# 02_MCU.net
KiCad netlist of a schematic drawn in Altium Designer
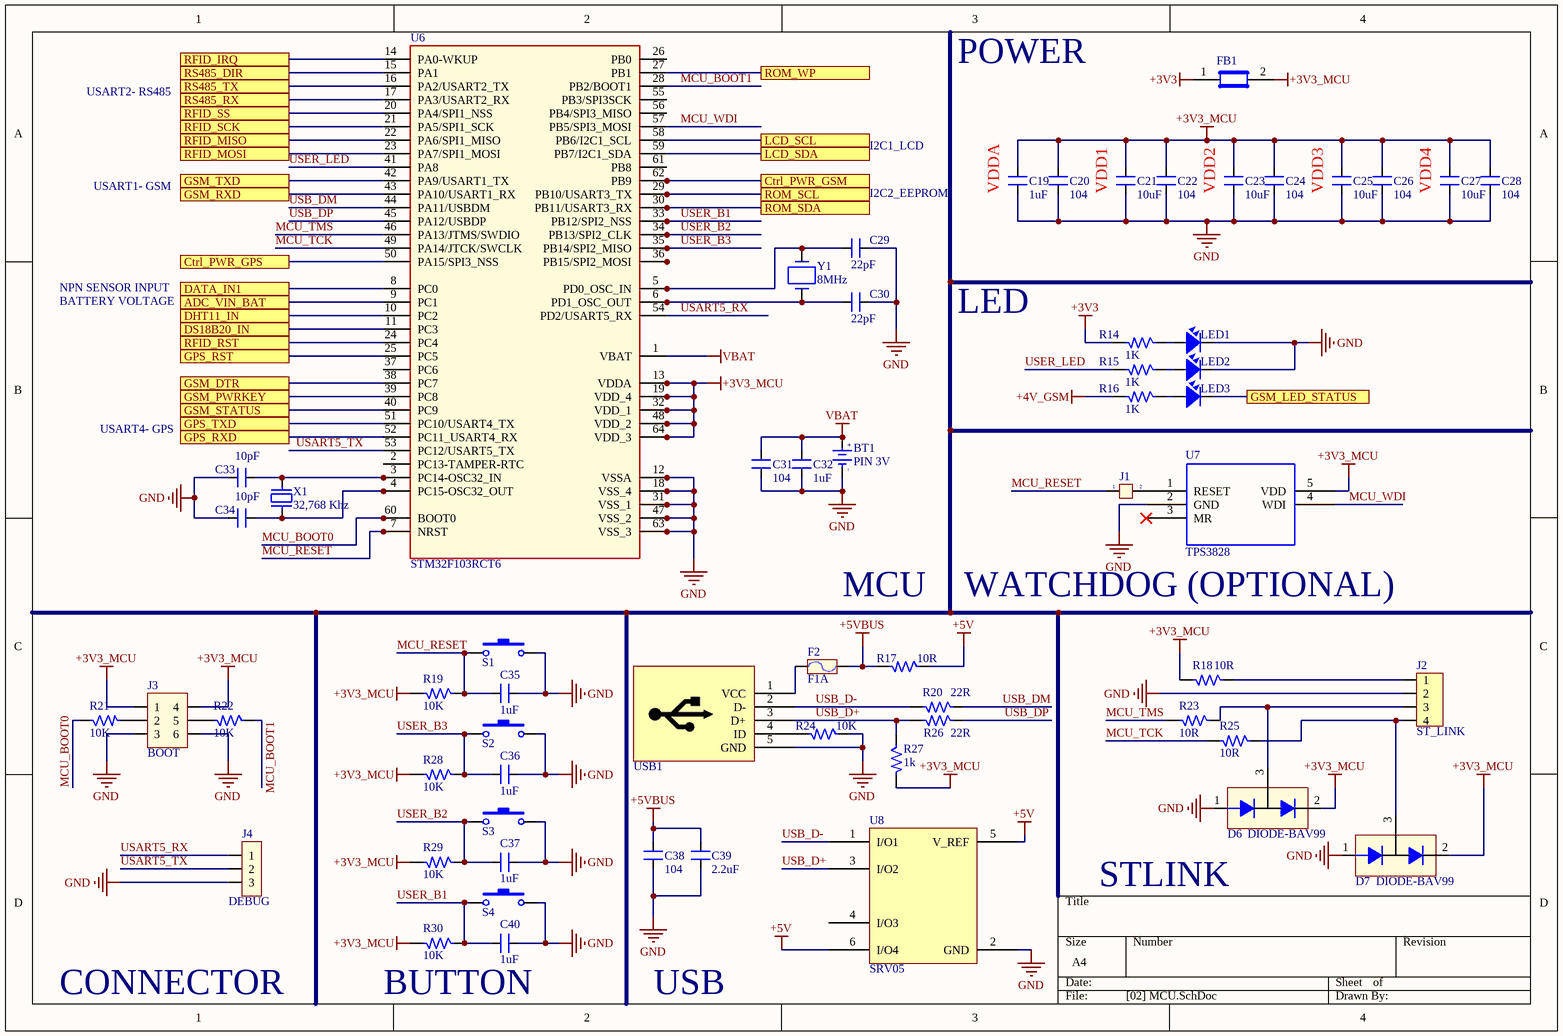
[diagram p0: [02] MCU.SchDoc]

(export (version "E")
  (design (tool "Eeschema 10.0.6"))
  (components
    (comp (ref "BT1")
      (value "PIN 3V")
      (footprint "CR1220 SMD")
      (description "Battery 3VDC")
      (libsource (lib "My Library") (part "PIN 3V"))
    )
    (comp (ref "C19")
      (value "1uF")
      (footprint "C0603 SMT")
      (description "Cap SMD")
      (libsource (lib "GPS_Traking_V1_1") (part "CM"))
    )
    (comp (ref "C20")
      (value "104")
      (footprint "C0603 SMT")
      (description "Cap SMD")
      (libsource (lib "GPS_Traking_V1_1") (part "CM"))
    )
    (comp (ref "C21")
      (value "10uF")
      (footprint "C0603 SMT")
      (description "Cap SMD")
      (libsource (lib "GPS_Traking_V1_1") (part "CM"))
    )
    (comp (ref "C22")
      (value "104")
      (footprint "C0603 SMT")
      (description "Cap SMD")
      (libsource (lib "GPS_Traking_V1_1") (part "CM"))
    )
    (comp (ref "C23")
      (value "10uF")
      (footprint "C0603 SMT")
      (description "Cap SMD")
      (libsource (lib "GPS_Traking_V1_1") (part "CM"))
    )
    (comp (ref "C24")
      (value "104")
      (footprint "C0603 SMT")
      (description "Cap SMD")
      (libsource (lib "GPS_Traking_V1_1") (part "CM"))
    )
    (comp (ref "C25")
      (value "10uF")
      (footprint "C0603 SMT")
      (description "Cap SMD")
      (libsource (lib "GPS_Traking_V1_1") (part "CM"))
    )
    (comp (ref "C26")
      (value "104")
      (footprint "C0603 SMT")
      (description "Cap SMD")
      (libsource (lib "GPS_Traking_V1_1") (part "CM"))
    )
    (comp (ref "C27")
      (value "10uF")
      (footprint "C0603 SMT")
      (description "Cap SMD")
      (libsource (lib "GPS_Traking_V1_1") (part "CM"))
    )
    (comp (ref "C28")
      (value "104")
      (footprint "C0603 SMT")
      (description "Cap SMD")
      (libsource (lib "GPS_Traking_V1_1") (part "CM"))
    )
    (comp (ref "C29")
      (value "22pF")
      (footprint "C0603 SMT")
      (description "Cap SMD")
      (libsource (lib "GPS_Traking_V1_1") (part "CM"))
    )
    (comp (ref "C30")
      (value "22pF")
      (footprint "GPS_Traking_V1_1:C0603 SMT")
      (description "Cap SMD")
      (libsource (lib "My Library") (part "CM"))
    )
    (comp (ref "C31")
      (value "104")
      (footprint "C0603 SMT")
      (description "Cap SMD")
      (libsource (lib "GPS_Traking_V1_1") (part "CM"))
    )
    (comp (ref "C32")
      (value "1uF")
      (footprint "GPS_Traking_V1_1:C0603 SMT")
      (description "Cap SMD")
      (libsource (lib "My Library") (part "CM"))
    )
    (comp (ref "C33")
      (value "10pF")
      (footprint "C0603 SMT")
      (description "Cap SMD")
      (libsource (lib "GPS_Traking_V1_1") (part "CM"))
    )
    (comp (ref "C34")
      (value "10pF")
      (footprint "C0603 SMT")
      (description "Cap SMD")
      (libsource (lib "GPS_Traking_V1_1") (part "CM"))
    )
    (comp (ref "C35")
      (value "1uF")
      (footprint "CAP_0805")
      (description "Cap SMD")
      (libsource (lib "GPS_Traking_V1_1") (part "CM"))
    )
    (comp (ref "C36")
      (value "1uF")
      (footprint "CAP_0805")
      (description "Cap SMD")
      (libsource (lib "GPS_Traking_V1_1") (part "CM"))
    )
    (comp (ref "C37")
      (value "1uF")
      (footprint "CAP_0805")
      (description "Cap SMD")
      (libsource (lib "GPS_Traking_V1_1") (part "CM"))
    )
    (comp (ref "C38")
      (value "104")
      (footprint "C0603 SMT")
      (description "Cap SMD")
      (libsource (lib "GPS_Traking_V1_1") (part "CM"))
    )
    (comp (ref "C39")
      (value "2.2uF")
      (footprint "RES-SMD-1210")
      (description "Cap SMD")
      (libsource (lib "My Library") (part "CM"))
    )
    (comp (ref "C40")
      (value "1uF")
      (footprint "CAP_0805")
      (description "Cap SMD")
      (libsource (lib "GPS_Traking_V1_1") (part "CM"))
    )
    (comp (ref "D6")
      (value "DIODE-BAV99")
      (footprint "SOT23")
      (description "ZENER, SOT23,")
      (fields
        (field (name "MANUFACTURER") "ON Semiconductor / Fairchild")
        (field (name "MANUFACTURER PART NUMBER") "BAV99")
        (field (name ".CREATOR") "LeKhaLinh")
        (field (name ".CHECKPCB") "LeKhaLinh")
        (field (name ".CHECKSCH") "LeKhaLinh")
      )
      (libsource (lib "GPS_Traking_V1_1") (part "DIODE-BAV99"))
    )
    (comp (ref "D7")
      (value "DIODE-BAV99")
      (footprint "SOT23")
      (description "ZENER, SOT23,")
      (fields
        (field (name "MANUFACTURER") "ON Semiconductor / Fairchild")
        (field (name "MANUFACTURER PART NUMBER") "BAV99")
        (field (name ".CREATOR") "LeKhaLinh")
        (field (name ".CHECKPCB") "LeKhaLinh")
        (field (name ".CHECKSCH") "LeKhaLinh")
      )
      (libsource (lib "GPS_Traking_V1_1") (part "DIODE-BAV99"))
    )
    (comp (ref "F2")
      (value "F1A")
      (footprint "RES-SMD-1812")
      (description "Fuse")
      (fields (field (name "DESIGNED BY") "VanDungEvn"))
      (libsource (lib "My Library") (part "Fuse"))
    )
    (comp (ref "FB1")
      (value "BLM21PG600SN1D")
      (footprint "GPS_Traking_V1_1:R0805")
      (description "Ferrite Bead")
      (libsource (lib "khapham") (part "Ferrite Bead"))
    )
    (comp (ref "J1")
      (value "watdog")
      (footprint "JP2")
      (description "Jumper 2")
      (libsource (lib "GPS_Traking_V1_1") (part "JP 2"))
    )
    (comp (ref "J2")
      (value "ST_LINK")
      (footprint "CON_4P")
      (description "Header IDC, 4 x 1 Pin Vertical 2.54mm Pitch (Non-Boxed, Male)")
      (fields
        (field (name "MANUFACTURER") "Würth Elektronik eiSos GmbH")
        (field (name "PARTNO") "613002143121")
        (field (name "CREATED BY") "Karrer Zheng")
      )
      (libsource (lib "My Library") (part "Header4"))
    )
    (comp (ref "J3")
      (value "BOOT")
      (footprint "JP3x2")
      (description "Connector 3x2")
      (libsource (lib "GPS_Traking_V1_1") (part "JP3x2"))
    )
    (comp (ref "J4")
      (value "DEBUG")
      (footprint "JP3")
      (description "Jumper 3")
      (libsource (lib "My Library") (part "JP3"))
    )
    (comp (ref "LED1")
      (value "LED")
      (footprint "LED-0805-Green")
      (description "LED Single colour Green and Red")
      (libsource (lib "My Library") (part "LED"))
    )
    (comp (ref "LED2")
      (value "LED")
      (footprint "LED-0805-Yellow")
      (description "LED Single colour Green and Red")
      (libsource (lib "My Library") (part "LED"))
    )
    (comp (ref "LED3")
      (value "LED")
      (footprint "LED-0805-Red")
      (description "LED Single colour Green and Red")
      (libsource (lib "My Library") (part "LED"))
    )
    (comp (ref "R14")
      (value "1K")
      (footprint "RES-SMD-0805")
      (description "Resistor SMD")
      (libsource (lib "GPS_Traking_V1_1") (part "RM"))
    )
    (comp (ref "R15")
      (value "1K")
      (footprint "RES-SMD-0805")
      (description "Resistor SMD")
      (libsource (lib "GPS_Traking_V1_1") (part "RM"))
    )
    (comp (ref "R16")
      (value "1K")
      (footprint "RES-SMD-0805")
      (description "Resistor SMD")
      (libsource (lib "GPS_Traking_V1_1") (part "RM"))
    )
    (comp (ref "R17")
      (value "10R")
      (footprint "RES-SMD-0805")
      (description "Resistor SMD")
      (libsource (lib "GPS_Traking_V1_1") (part "RM"))
    )
    (comp (ref "R18")
      (value "10R")
      (footprint "RES-SMD-0805")
      (description "Resistor SMD")
      (libsource (lib "GPS_Traking_V1_1") (part "RM"))
    )
    (comp (ref "R19")
      (value "10K")
      (footprint "RES-SMD-0805")
      (description "Resistor SMD")
      (libsource (lib "GPS_Traking_V1_1") (part "RM"))
    )
    (comp (ref "R20")
      (value "22R")
      (footprint "RES-SMD-0603")
      (description "Resistor SMD")
      (libsource (lib "GPS_Traking_V1_1") (part "RM"))
    )
    (comp (ref "R21")
      (value "10K")
      (footprint "R0603 -SMT")
      (description "Resistor SMD")
      (libsource (lib "GPS_Traking_V1_1") (part "RM"))
    )
    (comp (ref "R22")
      (value "10K")
      (footprint "R0603 -SMT")
      (description "Resistor SMD")
      (libsource (lib "GPS_Traking_V1_1") (part "RM"))
    )
    (comp (ref "R23")
      (value "10R")
      (footprint "RES-SMD-0805")
      (description "Resistor SMD")
      (libsource (lib "GPS_Traking_V1_1") (part "RM"))
    )
    (comp (ref "R24")
      (value "10K")
      (footprint "RES-SMD-0603")
      (description "Resistor SMD")
      (libsource (lib "GPS_Traking_V1_1") (part "RM"))
    )
    (comp (ref "R25")
      (value "10R")
      (footprint "RES-SMD-0805")
      (description "Resistor SMD")
      (libsource (lib "GPS_Traking_V1_1") (part "RM"))
    )
    (comp (ref "R26")
      (value "22R")
      (footprint "RES-SMD-0603")
      (description "Resistor SMD")
      (libsource (lib "GPS_Traking_V1_1") (part "RM"))
    )
    (comp (ref "R27")
      (value "1k")
      (footprint "RES-SMD-0603")
      (description "Resistor SMD")
      (libsource (lib "GPS_Traking_V1_1") (part "RM"))
    )
    (comp (ref "R28")
      (value "10K")
      (footprint "RES-SMD-0805")
      (description "Resistor SMD")
      (libsource (lib "GPS_Traking_V1_1") (part "RM"))
    )
    (comp (ref "R29")
      (value "10K")
      (footprint "RES-SMD-0805")
      (description "Resistor SMD")
      (libsource (lib "GPS_Traking_V1_1") (part "RM"))
    )
    (comp (ref "R30")
      (value "10K")
      (footprint "RES-SMD-0805")
      (description "Resistor SMD")
      (libsource (lib "GPS_Traking_V1_1") (part "RM"))
    )
    (comp (ref "S1")
      (value "SW-SMD")
      (footprint "SW-SMD")
      (description "Switch")
      (fields (field (name "PUBLISHER") "Altium Limited"))
      (libsource (lib "My Library") (part "SW-SMD"))
    )
    (comp (ref "S2")
      (value "SW-SMD")
      (footprint "BUTTON NGHIENG")
      (description "Switch")
      (fields (field (name "PUBLISHER") "Altium Limited"))
      (libsource (lib "My Library") (part "SW-SMD"))
    )
    (comp (ref "S3")
      (value "SW-SMD")
      (footprint "BUTTON NGHIENG")
      (description "Switch")
      (fields (field (name "PUBLISHER") "Altium Limited"))
      (libsource (lib "My Library") (part "SW-SMD"))
    )
    (comp (ref "S4")
      (value "SW-SMD")
      (footprint "BUTTON NGHIENG")
      (description "Switch")
      (fields (field (name "PUBLISHER") "Altium Limited"))
      (libsource (lib "My Library") (part "SW-SMD"))
    )
    (comp (ref "U6")
      (value "STM32F103RCT6")
      (footprint "LQFP-64")
      (description "MCU 32BIT 256KB FLASH 64LQFP")
      (libsource (lib "GPS_Traking_V1_1") (part "STM32F103RCT6"))
    )
    (comp (ref "U7")
      (value "TPS3828")
      (footprint "TPS3828")
      (libsource (lib "GPS_Traking_V1_1") (part "TPS3828"))
    )
    (comp (ref "U8")
      (value "SRV05")
      (footprint "SOT23-6")
      (description "TVS DIODE 5V")
      (libsource (lib "My Library") (part "SRV05"))
    )
    (comp (ref "USB1") (value "USB") (footprint "USB-B-Mini") (libsource (lib "My Library") (part "USB-M")))
    (comp (ref "X1")
      (value "32,768 Khz")
      (footprint "XT32kn")
      (description "Crystal 32,768kHz for timer real")
      (libsource (lib "GPS_Traking_V1_1") (part "XT32k"))
    )
    (comp (ref "Y1")
      (value "8MHz")
      (footprint "GPS_Traking_V1_1:ABM7_v1_1_BIG")
      (description "CRYSTAL 16MHZ 18PF SMD")
      (fields
        (field (name "MANUFACTURER") "Abracon LLC")
        (field (name "MANUFACTURER PART NUMBER") "ABM7-16.000MHZ-D2Y-T")
        (field (name ".CREATOR") "MM")
        (field (name ".CHECKED PCB") "RF")
        (field (name ".CHECKED SCH") "RF")
      )
      (libsource (lib "GPS_Traking_V1_1") (part "ABM7-16.000MHZ-D2Y-T"))
    )
  )
  (nets
    (net (code "1") (name "+3V3") (class "Default")
      (node (ref "FB1") (pin "1") (pinfunction "1_1") (pintype "passive"))
      (node (ref "R14") (pin "2") (pinfunction "2_2") (pintype "passive"))
    )
    (net (code "2") (name "+3V3_MCU") (class "Default")
      (node (ref "C19") (pin "2") (pinfunction "2_2") (pintype "passive"))
      (node (ref "C20") (pin "2") (pinfunction "2_2") (pintype "passive"))
      (node (ref "C21") (pin "2") (pinfunction "2_2") (pintype "passive"))
      (node (ref "C22") (pin "2") (pinfunction "2_2") (pintype "passive"))
      (node (ref "C23") (pin "2") (pinfunction "2_2") (pintype "passive"))
      (node (ref "C24") (pin "2") (pinfunction "2_2") (pintype "passive"))
      (node (ref "C25") (pin "2") (pinfunction "2_2") (pintype "passive"))
      (node (ref "C26") (pin "2") (pinfunction "2_2") (pintype "passive"))
      (node (ref "C27") (pin "2") (pinfunction "2_2") (pintype "passive"))
      (node (ref "C28") (pin "2") (pinfunction "2_2") (pintype "passive"))
      (node (ref "D6") (pin "2") (pinfunction "2_2") (pintype "passive"))
      (node (ref "D7") (pin "2") (pinfunction "2_2") (pintype "passive"))
      (node (ref "FB1") (pin "2") (pinfunction "2_2") (pintype "passive"))
      (node (ref "J3") (pin "1") (pinfunction "1_1") (pintype "passive"))
      (node (ref "J3") (pin "4") (pinfunction "4_4") (pintype "passive"))
      (node (ref "R18") (pin "2") (pinfunction "2_2") (pintype "passive"))
      (node (ref "R19") (pin "2") (pinfunction "2_2") (pintype "passive"))
      (node (ref "R27") (pin "2") (pinfunction "2_2") (pintype "passive"))
      (node (ref "R28") (pin "2") (pinfunction "2_2") (pintype "passive"))
      (node (ref "R29") (pin "2") (pinfunction "2_2") (pintype "passive"))
      (node (ref "R30") (pin "2") (pinfunction "2_2") (pintype "passive"))
      (node (ref "U6") (pin "13") (pinfunction "VDDA_13") (pintype "passive"))
      (node (ref "U6") (pin "19") (pinfunction "VDD_4_19") (pintype "passive"))
      (node (ref "U6") (pin "32") (pinfunction "VDD_1_32") (pintype "passive"))
      (node (ref "U6") (pin "48") (pinfunction "VDD_2_48") (pintype "passive"))
      (node (ref "U6") (pin "64") (pinfunction "VDD_3_64") (pintype "passive"))
      (node (ref "U7") (pin "5") (pinfunction "VDD_5") (pintype "power_in"))
    )
    (net (code "3") (name "+4V_GSM") (class "Default")
      (node (ref "R16") (pin "2") (pinfunction "2_2") (pintype "passive"))
    )
    (net (code "4") (name "+5V") (class "Default")
      (node (ref "R17") (pin "1") (pinfunction "1_1") (pintype "passive"))
      (node (ref "U8") (pin "5") (pinfunction "V_REF_5") (pintype "passive"))
      (node (ref "U8") (pin "6") (pinfunction "I/O4_6") (pintype "passive"))
    )
    (net (code "5") (name "+5VBUS") (class "Default")
      (node (ref "C38") (pin "2") (pinfunction "2_2") (pintype "passive"))
      (node (ref "C39") (pin "2") (pinfunction "2_2") (pintype "passive"))
      (node (ref "F2") (pin "2") (pinfunction "2_2") (pintype "passive"))
      (node (ref "R17") (pin "2") (pinfunction "2_2") (pintype "passive"))
    )
    (net (code "6") (name "/ADC_VIN_BAT") (class "Default")
      (node (ref "U6") (pin "9") (pinfunction "PC1_9") (pintype "passive"))
    )
    (net (code "7") (name "/Ctrl_PWR_GPS") (class "Default")
      (node (ref "U6") (pin "50") (pinfunction "PA15/SPI3_NSS_50") (pintype "passive"))
    )
    (net (code "8") (name "/Ctrl_PWR_GSM") (class "Default")
      (node (ref "U6") (pin "62") (pinfunction "PB9_62") (pintype "passive"))
    )
    (net (code "9") (name "/DATA_IN1") (class "Default")
      (node (ref "U6") (pin "8") (pinfunction "PC0_8") (pintype "passive"))
    )
    (net (code "10") (name "/DHT11_IN") (class "Default")
      (node (ref "U6") (pin "10") (pinfunction "PC2_10") (pintype "passive"))
    )
    (net (code "11") (name "/DS18B20_IN") (class "Default")
      (node (ref "U6") (pin "11") (pinfunction "PC3_11") (pintype "passive"))
    )
    (net (code "12") (name "/GPS_RST") (class "Default")
      (node (ref "U6") (pin "25") (pinfunction "PC5_25") (pintype "passive"))
    )
    (net (code "13") (name "/GPS_RXD") (class "Default")
      (node (ref "U6") (pin "52") (pinfunction "PC11_USART4_RX_52") (pintype "passive"))
    )
    (net (code "14") (name "/GPS_TXD") (class "Default")
      (node (ref "U6") (pin "51") (pinfunction "PC10/USART4_TX_51") (pintype "passive"))
    )
    (net (code "15") (name "/GSM_DTR") (class "Default")
      (node (ref "U6") (pin "38") (pinfunction "PC7_38") (pintype "passive"))
    )
    (net (code "16") (name "/GSM_LED_STATUS") (class "Default")
      (node (ref "LED3") (pin "2") (pinfunction "2_2") (pintype "passive"))
    )
    (net (code "17") (name "/GSM_PWRKEY") (class "Default")
      (node (ref "U6") (pin "39") (pinfunction "PC8_39") (pintype "passive"))
    )
    (net (code "18") (name "/GSM_RXD") (class "Default")
      (node (ref "U6") (pin "43") (pinfunction "PA10/USART1_RX_43") (pintype "passive"))
    )
    (net (code "19") (name "/GSM_STATUS") (class "Default")
      (node (ref "U6") (pin "40") (pinfunction "PC9_40") (pintype "passive"))
    )
    (net (code "20") (name "/GSM_TXD") (class "Default")
      (node (ref "U6") (pin "42") (pinfunction "PA9/USART1_TX_42") (pintype "passive"))
    )
    (net (code "21") (name "/LCD_SCL") (class "Default")
      (node (ref "U6") (pin "58") (pinfunction "PB6/I2C1_SCL_58") (pintype "passive"))
    )
    (net (code "22") (name "/LCD_SDA") (class "Default")
      (node (ref "U6") (pin "59") (pinfunction "PB7/I2C1_SDA_59") (pintype "passive"))
    )
    (net (code "23") (name "/MCU_BOOT0") (class "Default")
      (node (ref "R21") (pin "1") (pinfunction "1_1") (pintype "passive"))
      (node (ref "U6") (pin "60") (pinfunction "BOOT0_60") (pintype "passive"))
    )
    (net (code "24") (name "/MCU_BOOT1") (class "Default")
      (node (ref "R22") (pin "1") (pinfunction "1_1") (pintype "passive"))
      (node (ref "U6") (pin "28") (pinfunction "PB2/BOOT1_28") (pintype "passive"))
    )
    (net (code "25") (name "/MCU_RESET") (class "Default")
      (node (ref "C35") (pin "1") (pinfunction "1_1") (pintype "passive"))
      (node (ref "J1") (pin "1") (pinfunction "1_1") (pintype "passive"))
      (node (ref "R19") (pin "1") (pinfunction "1_1") (pintype "passive"))
      (node (ref "S1") (pin "1") (pinfunction "1_1") (pintype "passive"))
      (node (ref "U6") (pin "7") (pinfunction "NRST_7") (pintype "passive"))
    )
    (net (code "26") (name "/MCU_TCK") (class "Default")
      (node (ref "R25") (pin "2") (pinfunction "2_2") (pintype "passive"))
      (node (ref "U6") (pin "49") (pinfunction "PA14/JTCK/SWCLK_49") (pintype "passive"))
    )
    (net (code "27") (name "/MCU_TMS") (class "Default")
      (node (ref "R23") (pin "2") (pinfunction "2_2") (pintype "passive"))
      (node (ref "U6") (pin "46") (pinfunction "PA13/JTMS/SWDIO_46") (pintype "passive"))
    )
    (net (code "28") (name "/MCU_WDI") (class "Default")
      (node (ref "U6") (pin "57") (pinfunction "PB5/SPI3_MOSI_57") (pintype "passive"))
      (node (ref "U7") (pin "4") (pinfunction "WDI_4") (pintype "passive"))
    )
    (net (code "29") (name "/RFID_IRQ") (class "Default")
      (node (ref "U6") (pin "14") (pinfunction "PA0-WKUP_14") (pintype "passive"))
    )
    (net (code "30") (name "/RFID_MISO") (class "Default")
      (node (ref "U6") (pin "22") (pinfunction "PA6/SPI1_MISO_22") (pintype "passive"))
    )
    (net (code "31") (name "/RFID_MOSI") (class "Default")
      (node (ref "U6") (pin "23") (pinfunction "PA7/SPI1_MOSI_23") (pintype "passive"))
    )
    (net (code "32") (name "/RFID_RST") (class "Default")
      (node (ref "U6") (pin "24") (pinfunction "PC4_24") (pintype "passive"))
    )
    (net (code "33") (name "/RFID_SCK") (class "Default")
      (node (ref "U6") (pin "21") (pinfunction "PA5/SPI1_SCK_21") (pintype "passive"))
    )
    (net (code "34") (name "/RFID_SS") (class "Default")
      (node (ref "U6") (pin "20") (pinfunction "PA4/SPI1_NSS_20") (pintype "passive"))
    )
    (net (code "35") (name "/ROM_SCL") (class "Default")
      (node (ref "U6") (pin "29") (pinfunction "PB10/USART3_TX_29") (pintype "passive"))
    )
    (net (code "36") (name "/ROM_SDA") (class "Default")
      (node (ref "U6") (pin "30") (pinfunction "PB11/USART3_RX_30") (pintype "passive"))
    )
    (net (code "37") (name "/ROM_WP") (class "Default")
      (node (ref "U6") (pin "27") (pinfunction "PB1_27") (pintype "passive"))
    )
    (net (code "38") (name "/RS485_DIR") (class "Default")
      (node (ref "U6") (pin "15") (pinfunction "PA1_15") (pintype "passive"))
    )
    (net (code "39") (name "/RS485_RX") (class "Default")
      (node (ref "U6") (pin "17") (pinfunction "PA3/USART2_RX_17") (pintype "passive"))
    )
    (net (code "40") (name "/RS485_TX") (class "Default")
      (node (ref "U6") (pin "16") (pinfunction "PA2/USART2_TX_16") (pintype "passive"))
    )
    (net (code "41") (name "/USART5_RX") (class "Default")
      (node (ref "J4") (pin "1") (pinfunction "1_1") (pintype "passive"))
      (node (ref "U6") (pin "54") (pinfunction "PD2/USART5_RX_54") (pintype "passive"))
    )
    (net (code "42") (name "/USART5_TX") (class "Default")
      (node (ref "J4") (pin "2") (pinfunction "2_2") (pintype "passive"))
      (node (ref "U6") (pin "53") (pinfunction "PC12/USART5_TX_53") (pintype "passive"))
    )
    (net (code "43") (name "/USB_D+") (class "Default")
      (node (ref "R26") (pin "2") (pinfunction "2_2") (pintype "passive"))
      (node (ref "R27") (pin "1") (pinfunction "1_1") (pintype "passive"))
      (node (ref "U8") (pin "3") (pinfunction "I/O2_3") (pintype "passive"))
      (node (ref "USB1") (pin "3") (pinfunction "D+_3") (pintype "passive"))
    )
    (net (code "44") (name "/USB_D-") (class "Default")
      (node (ref "R20") (pin "2") (pinfunction "2_2") (pintype "passive"))
      (node (ref "U8") (pin "1") (pinfunction "I/O1_1") (pintype "passive"))
      (node (ref "USB1") (pin "2") (pinfunction "D-_2") (pintype "passive"))
    )
    (net (code "45") (name "/USB_DM") (class "Default")
      (node (ref "R20") (pin "1") (pinfunction "1_1") (pintype "passive"))
      (node (ref "U6") (pin "44") (pinfunction "PA11/USBDM_44") (pintype "passive"))
    )
    (net (code "46") (name "/USB_DP") (class "Default")
      (node (ref "R26") (pin "1") (pinfunction "1_1") (pintype "passive"))
      (node (ref "U6") (pin "45") (pinfunction "PA12/USBDP_45") (pintype "passive"))
    )
    (net (code "47") (name "/USER_B1") (class "Default")
      (node (ref "C40") (pin "1") (pinfunction "1_1") (pintype "passive"))
      (node (ref "R30") (pin "1") (pinfunction "1_1") (pintype "passive"))
      (node (ref "S4") (pin "1") (pinfunction "1_1") (pintype "passive"))
      (node (ref "U6") (pin "33") (pinfunction "PB12/SPI2_NSS_33") (pintype "passive"))
    )
    (net (code "48") (name "/USER_B2") (class "Default")
      (node (ref "C37") (pin "1") (pinfunction "1_1") (pintype "passive"))
      (node (ref "R29") (pin "1") (pinfunction "1_1") (pintype "passive"))
      (node (ref "S3") (pin "1") (pinfunction "1_1") (pintype "passive"))
      (node (ref "U6") (pin "34") (pinfunction "PB13/SPI2_CLK_34") (pintype "passive"))
    )
    (net (code "49") (name "/USER_B3") (class "Default")
      (node (ref "C36") (pin "1") (pinfunction "1_1") (pintype "passive"))
      (node (ref "R28") (pin "1") (pinfunction "1_1") (pintype "passive"))
      (node (ref "S2") (pin "1") (pinfunction "1_1") (pintype "passive"))
      (node (ref "U6") (pin "35") (pinfunction "PB14/SPI2_MISO_35") (pintype "passive"))
    )
    (net (code "50") (name "/USER_LED") (class "Default")
      (node (ref "R15") (pin "2") (pinfunction "2_2") (pintype "passive"))
      (node (ref "U6") (pin "41") (pinfunction "PA8_41") (pintype "passive"))
    )
    (net (code "51") (name "GND") (class "Default")
      (node (ref "BT1") (pin "2") (pinfunction "GND_2") (pintype "passive"))
      (node (ref "C19") (pin "1") (pinfunction "1_1") (pintype "passive"))
      (node (ref "C20") (pin "1") (pinfunction "1_1") (pintype "passive"))
      (node (ref "C21") (pin "1") (pinfunction "1_1") (pintype "passive"))
      (node (ref "C22") (pin "1") (pinfunction "1_1") (pintype "passive"))
      (node (ref "C23") (pin "1") (pinfunction "1_1") (pintype "passive"))
      (node (ref "C24") (pin "1") (pinfunction "1_1") (pintype "passive"))
      (node (ref "C25") (pin "1") (pinfunction "1_1") (pintype "passive"))
      (node (ref "C26") (pin "1") (pinfunction "1_1") (pintype "passive"))
      (node (ref "C27") (pin "1") (pinfunction "1_1") (pintype "passive"))
      (node (ref "C28") (pin "1") (pinfunction "1_1") (pintype "passive"))
      (node (ref "C29") (pin "2") (pinfunction "2_2") (pintype "passive"))
      (node (ref "C30") (pin "2") (pinfunction "2_2") (pintype "passive"))
      (node (ref "C31") (pin "1") (pinfunction "1_1") (pintype "passive"))
      (node (ref "C32") (pin "1") (pinfunction "1_1") (pintype "passive"))
      (node (ref "C33") (pin "2") (pinfunction "2_2") (pintype "passive"))
      (node (ref "C34") (pin "2") (pinfunction "2_2") (pintype "passive"))
      (node (ref "C35") (pin "2") (pinfunction "2_2") (pintype "passive"))
      (node (ref "C36") (pin "2") (pinfunction "2_2") (pintype "passive"))
      (node (ref "C37") (pin "2") (pinfunction "2_2") (pintype "passive"))
      (node (ref "C38") (pin "1") (pinfunction "1_1") (pintype "passive"))
      (node (ref "C39") (pin "1") (pinfunction "1_1") (pintype "passive"))
      (node (ref "C40") (pin "2") (pinfunction "2_2") (pintype "passive"))
      (node (ref "D6") (pin "1") (pinfunction "1_1") (pintype "passive"))
      (node (ref "D7") (pin "1") (pinfunction "1_1") (pintype "passive"))
      (node (ref "J2") (pin "2") (pinfunction "2_2") (pintype "passive"))
      (node (ref "J3") (pin "3") (pinfunction "3_3") (pintype "passive"))
      (node (ref "J3") (pin "6") (pinfunction "6_6") (pintype "passive"))
      (node (ref "J4") (pin "3") (pinfunction "3_3") (pintype "passive"))
      (node (ref "LED1") (pin "2") (pinfunction "2_2") (pintype "passive"))
      (node (ref "LED2") (pin "2") (pinfunction "2_2") (pintype "passive"))
      (node (ref "R24") (pin "1") (pinfunction "1_1") (pintype "passive"))
      (node (ref "S1") (pin "2") (pinfunction "2_2") (pintype "passive"))
      (node (ref "S2") (pin "2") (pinfunction "2_2") (pintype "passive"))
      (node (ref "S3") (pin "2") (pinfunction "2_2") (pintype "passive"))
      (node (ref "S4") (pin "2") (pinfunction "2_2") (pintype "passive"))
      (node (ref "U6") (pin "12") (pinfunction "VSSA_12") (pintype "passive"))
      (node (ref "U6") (pin "18") (pinfunction "VSS_4_18") (pintype "passive"))
      (node (ref "U6") (pin "31") (pinfunction "VSS_1_31") (pintype "passive"))
      (node (ref "U6") (pin "47") (pinfunction "VSS_2_47") (pintype "passive"))
      (node (ref "U6") (pin "63") (pinfunction "VSS_3_63") (pintype "passive"))
      (node (ref "U7") (pin "2") (pinfunction "GND_2") (pintype "power_in"))
      (node (ref "U8") (pin "2") (pinfunction "GND_2") (pintype "passive"))
      (node (ref "USB1") (pin "5") (pinfunction "GND_5") (pintype "passive"))
    )
    (net (code "52") (name "Net-(D6-Pad3)") (class "Default")
      (node (ref "D6") (pin "3") (pinfunction "3_3") (pintype "passive"))
      (node (ref "J2") (pin "3") (pinfunction "3_3") (pintype "passive"))
      (node (ref "R23") (pin "1") (pinfunction "1_1") (pintype "passive"))
    )
    (net (code "53") (name "Net-(D7-Pad3)") (class "Default")
      (node (ref "D7") (pin "3") (pinfunction "3_3") (pintype "passive"))
      (node (ref "J2") (pin "4") (pinfunction "4_4") (pintype "passive"))
      (node (ref "R25") (pin "1") (pinfunction "1_1") (pintype "passive"))
    )
    (net (code "54") (name "Net-(J2-Pad1)") (class "Default")
      (node (ref "J2") (pin "1") (pinfunction "1_1") (pintype "passive"))
      (node (ref "R18") (pin "1") (pinfunction "1_1") (pintype "passive"))
    )
    (net (code "55") (name "Net-(J3-Pad2)") (class "Default")
      (node (ref "J3") (pin "2") (pinfunction "2_2") (pintype "passive"))
      (node (ref "R21") (pin "2") (pinfunction "2_2") (pintype "passive"))
    )
    (net (code "56") (name "Net-(J3-Pad5)") (class "Default")
      (node (ref "J3") (pin "5") (pinfunction "5_5") (pintype "passive"))
      (node (ref "R22") (pin "2") (pinfunction "2_2") (pintype "passive"))
    )
    (net (code "57") (name "Net-(LED1-Pad1)") (class "Default")
      (node (ref "LED1") (pin "1") (pinfunction "1_1") (pintype "passive"))
      (node (ref "R14") (pin "1") (pinfunction "1_1") (pintype "passive"))
    )
    (net (code "58") (name "Net-(LED2-Pad1)") (class "Default")
      (node (ref "LED2") (pin "1") (pinfunction "1_1") (pintype "passive"))
      (node (ref "R15") (pin "1") (pinfunction "1_1") (pintype "passive"))
    )
    (net (code "59") (name "Net-(LED3-Pad1)") (class "Default")
      (node (ref "LED3") (pin "1") (pinfunction "1_1") (pintype "passive"))
      (node (ref "R16") (pin "1") (pinfunction "1_1") (pintype "passive"))
    )
    (net (code "60") (name "Net-(U6-PC14-OSC32_IN)") (class "Default")
      (node (ref "C33") (pin "1") (pinfunction "1_1") (pintype "passive"))
      (node (ref "U6") (pin "3") (pinfunction "PC14-OSC32_IN_3") (pintype "passive"))
      (node (ref "X1") (pin "1") (pinfunction "1_1") (pintype "passive"))
    )
    (net (code "61") (name "Net-(U6-PC15-OSC32_OUT)") (class "Default")
      (node (ref "C34") (pin "1") (pinfunction "1_1") (pintype "passive"))
      (node (ref "U6") (pin "4") (pinfunction "PC15-OSC32_OUT_4") (pintype "passive"))
      (node (ref "X1") (pin "2") (pinfunction "2_2") (pintype "passive"))
    )
    (net (code "62") (name "Net-(U6-PD0_OSC_IN)") (class "Default")
      (node (ref "C29") (pin "1") (pinfunction "1_1") (pintype "passive"))
      (node (ref "U6") (pin "5") (pinfunction "PD0_OSC_IN_5") (pintype "passive"))
      (node (ref "Y1") (pin "2") (pinfunction "2_2") (pintype "passive"))
    )
    (net (code "63") (name "Net-(U6-PD1_OSC_OUT)") (class "Default")
      (node (ref "C30") (pin "1") (pinfunction "1_1") (pintype "passive"))
      (node (ref "U6") (pin "6") (pinfunction "PD1_OSC_OUT_6") (pintype "passive"))
      (node (ref "Y1") (pin "1") (pinfunction "1_1") (pintype "passive"))
    )
    (net (code "64") (name "Net-(U7-RESET)") (class "Default")
      (node (ref "J1") (pin "2") (pinfunction "2_2") (pintype "passive"))
      (node (ref "U7") (pin "1") (pinfunction "RESET_1") (pintype "passive"))
    )
    (net (code "65") (name "Net-(USB1-ID)") (class "Default")
      (node (ref "R24") (pin "2") (pinfunction "2_2") (pintype "passive"))
      (node (ref "USB1") (pin "4") (pinfunction "ID_4") (pintype "passive"))
    )
    (net (code "66") (name "Net-(USB1-VCC)") (class "Default")
      (node (ref "F2") (pin "1") (pinfunction "1_1") (pintype "passive"))
      (node (ref "USB1") (pin "1") (pinfunction "VCC_1") (pintype "passive"))
    )
    (net (code "67") (name "VBAT") (class "Default")
      (node (ref "BT1") (pin "1") (pinfunction "+3V_1") (pintype "passive"))
      (node (ref "C31") (pin "2") (pinfunction "2_2") (pintype "passive"))
      (node (ref "C32") (pin "2") (pinfunction "2_2") (pintype "passive"))
      (node (ref "U6") (pin "1") (pinfunction "VBAT_1") (pintype "passive"))
    )
    (net (code "68") (name "unconnected-(U6-PB0-Pad26)") (class "Default")
      (node (ref "U6") (pin "26") (pinfunction "PB0_26") (pintype "passive"))
    )
    (net (code "69") (name "unconnected-(U6-PB3{slash}SPI3SCK-Pad55)") (class "Default")
      (node (ref "U6") (pin "55") (pinfunction "PB3/SPI3SCK_55") (pintype "passive"))
    )
    (net (code "70") (name "unconnected-(U6-PB4{slash}SPI3_MISO-Pad56)") (class "Default")
      (node (ref "U6") (pin "56") (pinfunction "PB4/SPI3_MISO_56") (pintype "passive"))
    )
    (net (code "71") (name "unconnected-(U6-PB8-Pad61)") (class "Default")
      (node (ref "U6") (pin "61") (pinfunction "PB8_61") (pintype "passive"))
    )
    (net (code "72") (name "unconnected-(U6-PB15{slash}SPI2_MOSI-Pad36)") (class "Default")
      (node (ref "U6") (pin "36") (pinfunction "PB15/SPI2_MOSI_36") (pintype "passive"))
    )
    (net (code "73") (name "unconnected-(U6-PC6-Pad37)") (class "Default")
      (node (ref "U6") (pin "37") (pinfunction "PC6_37") (pintype "passive"))
    )
    (net (code "74") (name "unconnected-(U6-PC13-TAMPER-RTC-Pad2)") (class "Default")
      (node (ref "U6") (pin "2") (pinfunction "PC13-TAMPER-RTC_2") (pintype "passive"))
    )
    (net (code "75") (name "unconnected-(U7-MR-Pad3)") (class "Default")
      (node (ref "U7") (pin "3") (pinfunction "MR_3") (pintype "passive+no_connect"))
    )
    (net (code "76") (name "unconnected-(U8-I{slash}O3-Pad4)") (class "Default")
      (node (ref "U8") (pin "4") (pinfunction "I/O3_4") (pintype "passive"))
    )
  )
)
